# Voltage_Translators.net
KiCad netlist of a schematic drawn in Altium Designer
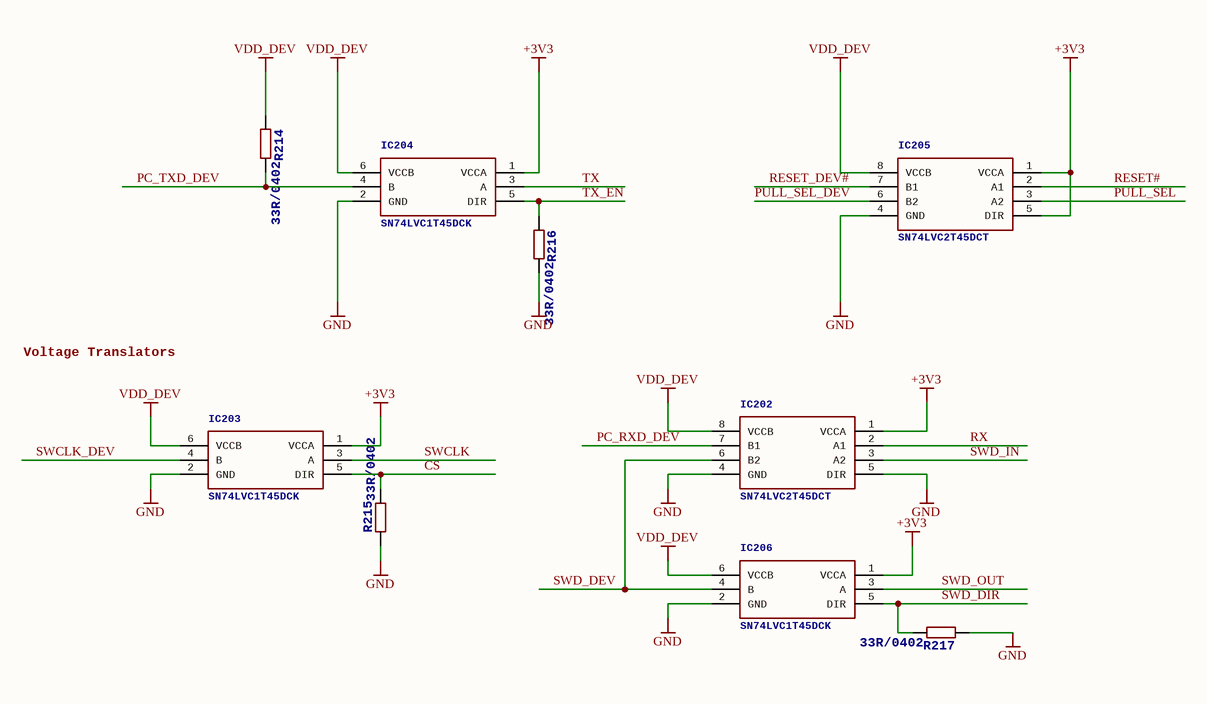
[diagram p0: Voltage Translators.SchDoc]

(export (version "E")
  (design (tool "Eeschema 10.0.6"))
  (components
    (comp (ref "IC202")
      (value "SN74LVC2T45DCT")
      (footprint "DCT_R-PDSO-G8")
      (libsource (lib "sucaiku") (part "SN74LVC2T45DCT"))
    )
    (comp (ref "IC203")
      (value "SN74LVC1T45DCK")
      (footprint "DCK_R-PDSO-G6")
      (libsource (lib "sucaiku") (part "SN74LVC1T45DCK"))
    )
    (comp (ref "IC204")
      (value "SN74LVC1T45DCK")
      (footprint "DCK_R-PDSO-G6")
      (libsource (lib "sucaiku") (part "SN74LVC1T45DCK"))
    )
    (comp (ref "IC205")
      (value "SN74LVC2T45DCT")
      (footprint "DCT_R-PDSO-G8")
      (libsource (lib "sucaiku") (part "SN74LVC2T45DCT"))
    )
    (comp (ref "IC206")
      (value "SN74LVC1T45DCK")
      (footprint "DCK_R-PDSO-G6")
      (libsource (lib "sucaiku") (part "SN74LVC1T45DCK"))
    )
    (comp (ref "R214") (value "33R/0402") (footprint "R0402") (libsource (lib "sucaiku") (part "R-EU_R0402")))
    (comp (ref "R215") (value "33R/0402") (footprint "R0402") (libsource (lib "sucaiku") (part "R-EU_R0402")))
    (comp (ref "R216") (value "33R/0402") (footprint "R0402") (libsource (lib "sucaiku") (part "R-EU_R0402")))
    (comp (ref "R217") (value "33R/0402") (footprint "R0402") (libsource (lib "sucaiku") (part "R-EU_R0402")))
  )
  (nets
    (net (code "1") (name "+3V3") (class "Default")
      (node (ref "IC202") (pin "1") (pinfunction "VCCA_1") (pintype "passive"))
      (node (ref "IC203") (pin "1") (pinfunction "VCCA_1") (pintype "passive"))
      (node (ref "IC204") (pin "1") (pinfunction "VCCA_1") (pintype "passive"))
      (node (ref "IC205") (pin "1") (pinfunction "VCCA_1") (pintype "passive"))
      (node (ref "IC205") (pin "5") (pinfunction "DIR_5") (pintype "passive"))
      (node (ref "IC206") (pin "1") (pinfunction "VCCA_1") (pintype "passive"))
    )
    (net (code "2") (name "/CS") (class "Default")
      (node (ref "IC203") (pin "5") (pinfunction "DIR_5") (pintype "passive"))
      (node (ref "R215") (pin "2") (pinfunction "2_2") (pintype "passive"))
    )
    (net (code "3") (name "/PC_RXD_DEV") (class "Default")
      (node (ref "IC202") (pin "7") (pinfunction "B1_7") (pintype "passive"))
    )
    (net (code "4") (name "/PC_TXD_DEV") (class "Default")
      (node (ref "IC204") (pin "4") (pinfunction "B_4") (pintype "passive"))
      (node (ref "R214") (pin "2") (pinfunction "2_2") (pintype "passive"))
    )
    (net (code "5") (name "/PULL_SEL") (class "Default")
      (node (ref "IC205") (pin "3") (pinfunction "A2_3") (pintype "passive"))
    )
    (net (code "6") (name "/PULL_SEL_DEV") (class "Default")
      (node (ref "IC205") (pin "6") (pinfunction "B2_6") (pintype "passive"))
    )
    (net (code "7") (name "/RESET#") (class "Default")
      (node (ref "IC205") (pin "2") (pinfunction "A1_2") (pintype "passive"))
    )
    (net (code "8") (name "/RESET_DEV#") (class "Default")
      (node (ref "IC205") (pin "7") (pinfunction "B1_7") (pintype "passive"))
    )
    (net (code "9") (name "/RX") (class "Default")
      (node (ref "IC202") (pin "2") (pinfunction "A1_2") (pintype "passive"))
    )
    (net (code "10") (name "/SWCLK") (class "Default")
      (node (ref "IC203") (pin "3") (pinfunction "A_3") (pintype "passive"))
    )
    (net (code "11") (name "/SWCLK_DEV") (class "Default")
      (node (ref "IC203") (pin "4") (pinfunction "B_4") (pintype "passive"))
    )
    (net (code "12") (name "/SWD_DEV") (class "Default")
      (node (ref "IC202") (pin "6") (pinfunction "B2_6") (pintype "passive"))
      (node (ref "IC206") (pin "4") (pinfunction "B_4") (pintype "passive"))
    )
    (net (code "13") (name "/SWD_DIR") (class "Default")
      (node (ref "IC206") (pin "5") (pinfunction "DIR_5") (pintype "passive"))
      (node (ref "R217") (pin "2") (pinfunction "2_2") (pintype "passive"))
    )
    (net (code "14") (name "/SWD_IN") (class "Default")
      (node (ref "IC202") (pin "3") (pinfunction "A2_3") (pintype "passive"))
    )
    (net (code "15") (name "/SWD_OUT") (class "Default")
      (node (ref "IC206") (pin "3") (pinfunction "A_3") (pintype "passive"))
    )
    (net (code "16") (name "/TX") (class "Default")
      (node (ref "IC204") (pin "3") (pinfunction "A_3") (pintype "passive"))
    )
    (net (code "17") (name "/TX_EN") (class "Default")
      (node (ref "IC204") (pin "5") (pinfunction "DIR_5") (pintype "passive"))
      (node (ref "R216") (pin "1") (pinfunction "1_1") (pintype "passive"))
    )
    (net (code "18") (name "GND") (class "Default")
      (node (ref "IC202") (pin "4") (pinfunction "GND_4") (pintype "passive"))
      (node (ref "IC202") (pin "5") (pinfunction "DIR_5") (pintype "passive"))
      (node (ref "IC203") (pin "2") (pinfunction "GND_2") (pintype "passive"))
      (node (ref "IC204") (pin "2") (pinfunction "GND_2") (pintype "passive"))
      (node (ref "IC205") (pin "4") (pinfunction "GND_4") (pintype "passive"))
      (node (ref "IC206") (pin "2") (pinfunction "GND_2") (pintype "passive"))
      (node (ref "R215") (pin "1") (pinfunction "1_1") (pintype "passive"))
      (node (ref "R216") (pin "2") (pinfunction "2_2") (pintype "passive"))
      (node (ref "R217") (pin "1") (pinfunction "1_1") (pintype "passive"))
    )
    (net (code "19") (name "VDD_DEV") (class "Default")
      (node (ref "IC202") (pin "8") (pinfunction "VCCB_8") (pintype "passive"))
      (node (ref "IC203") (pin "6") (pinfunction "VCCB_6") (pintype "passive"))
      (node (ref "IC204") (pin "6") (pinfunction "VCCB_6") (pintype "passive"))
      (node (ref "IC205") (pin "8") (pinfunction "VCCB_8") (pintype "passive"))
      (node (ref "IC206") (pin "6") (pinfunction "VCCB_6") (pintype "passive"))
      (node (ref "R214") (pin "1") (pinfunction "1_1") (pintype "passive"))
    )
  )
)
